# tachstrip.net
KiCad netlist of a schematic drawn in EAGLE
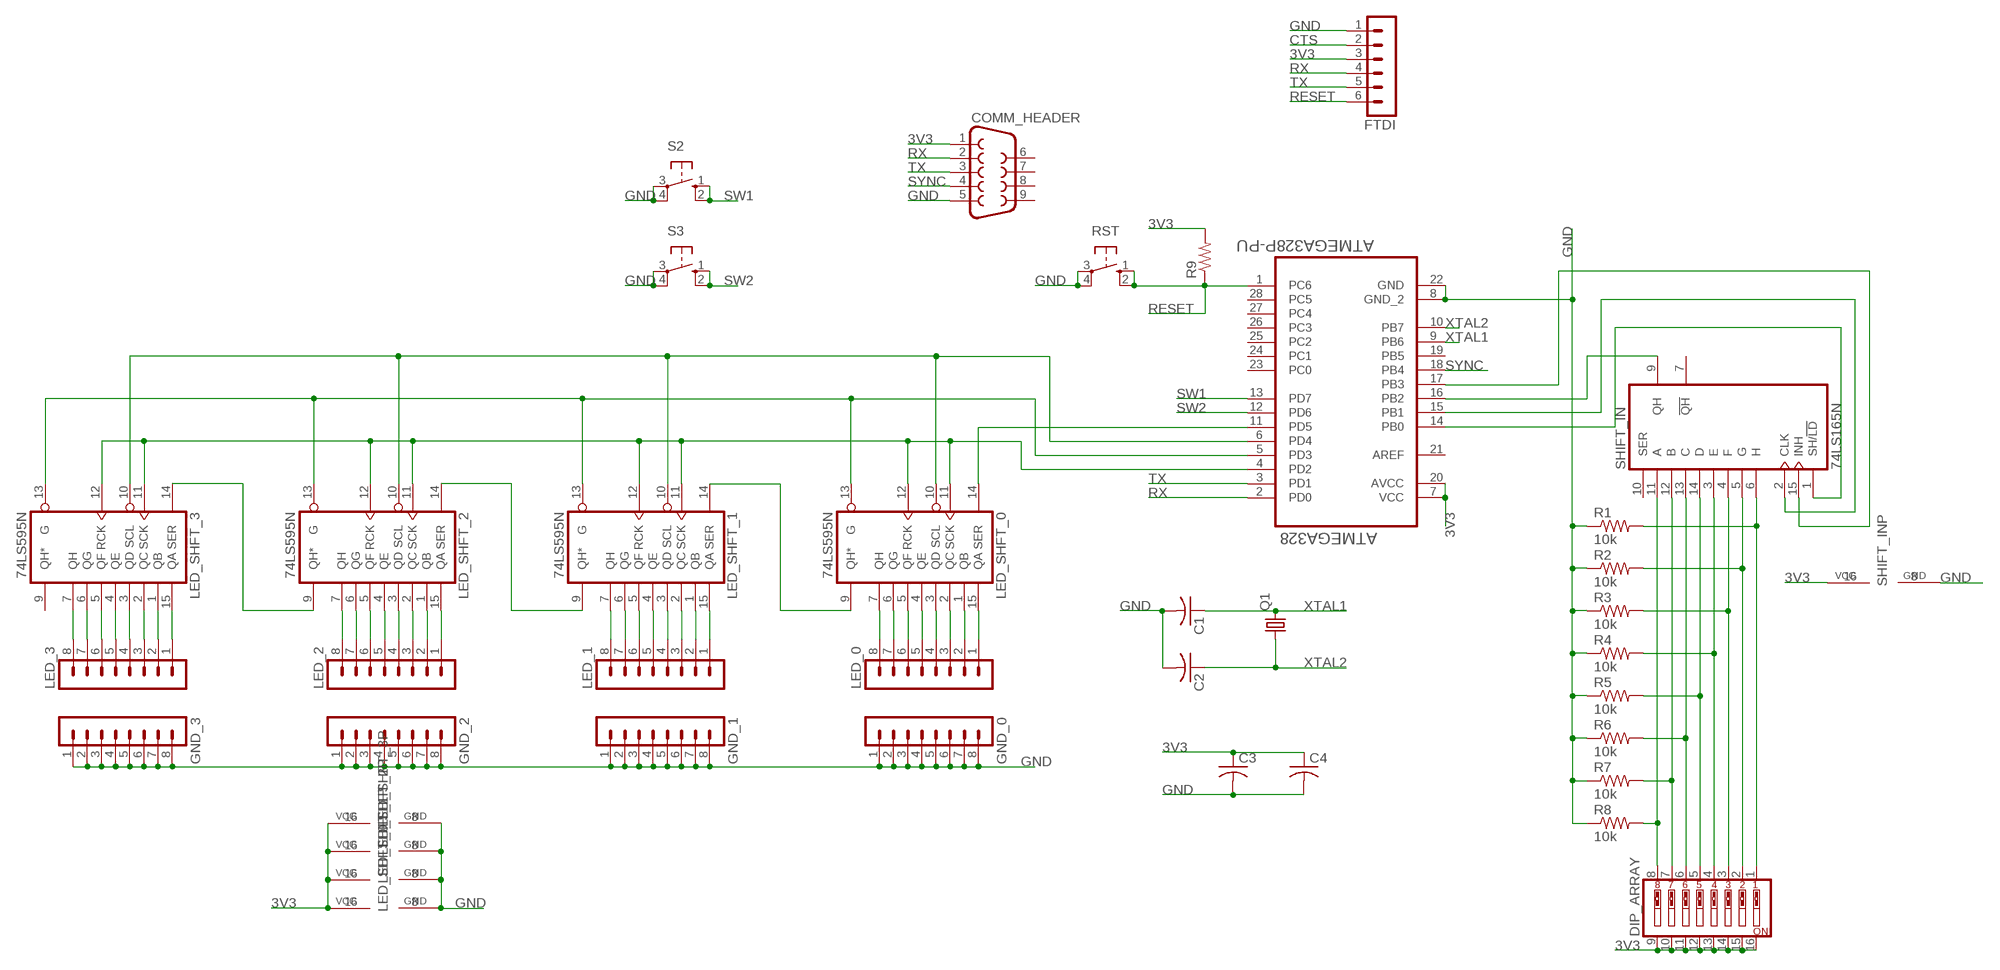
[diagram p0: schematic, sheet 1]

(export (version "E")
  (design (tool "Eeschema 10.0.6"))
  (components
    (comp (ref "ATMEGA328")
      (value "ATMEGA328P-PU")
      (footprint "eagle-import:DIP254P762X457-28")
      (libsource (lib "eagle-import") (part "ATMEGA328P-PU"))
    )
    (comp (ref "C1")
      (value "C-US025-025X050")
      (footprint "eagle-import:C025-025X050")
      (libsource (lib "eagle-import") (part "C-US025-025X050"))
    )
    (comp (ref "C2")
      (value "C-US025-025X050")
      (footprint "eagle-import:C025-025X050")
      (libsource (lib "eagle-import") (part "C-US025-025X050"))
    )
    (comp (ref "C3")
      (value "C-US025-025X050")
      (footprint "eagle-import:C025-025X050")
      (libsource (lib "eagle-import") (part "C-US025-025X050"))
    )
    (comp (ref "C4")
      (value "C-US025-025X050")
      (footprint "eagle-import:C025-025X050")
      (libsource (lib "eagle-import") (part "C-US025-025X050"))
    )
    (comp (ref "COMM_HEADER")
      (value "F09VB")
      (footprint "eagle-import:F09VB")
      (libsource (lib "eagle-import") (part "F09VB"))
    )
    (comp (ref "DIP_ARRAY")
      (value "SW_DIP-8")
      (footprint "eagle-import:DIPSWITCH-08")
      (libsource (lib "eagle-import") (part "SW_DIP-8"))
    )
    (comp (ref "FTDI")
      (value "MA06-1")
      (footprint "eagle-import:MA06-1")
      (libsource (lib "eagle-import") (part "MA06-1"))
    )
    (comp (ref "GND_0")
      (value "MA08-1")
      (footprint "eagle-import:MA08-1")
      (libsource (lib "eagle-import") (part "MA08-1"))
    )
    (comp (ref "GND_1")
      (value "MA08-1")
      (footprint "eagle-import:MA08-1")
      (libsource (lib "eagle-import") (part "MA08-1"))
    )
    (comp (ref "GND_2")
      (value "MA08-1")
      (footprint "eagle-import:MA08-1")
      (libsource (lib "eagle-import") (part "MA08-1"))
    )
    (comp (ref "GND_3")
      (value "MA08-1")
      (footprint "eagle-import:MA08-1")
      (libsource (lib "eagle-import") (part "MA08-1"))
    )
    (comp (ref "LED_0")
      (value "MA08-1")
      (footprint "eagle-import:MA08-1")
      (libsource (lib "eagle-import") (part "MA08-1"))
    )
    (comp (ref "LED_1")
      (value "MA08-1")
      (footprint "eagle-import:MA08-1")
      (libsource (lib "eagle-import") (part "MA08-1"))
    )
    (comp (ref "LED_2")
      (value "MA08-1")
      (footprint "eagle-import:MA08-1")
      (libsource (lib "eagle-import") (part "MA08-1"))
    )
    (comp (ref "LED_3")
      (value "MA08-1")
      (footprint "eagle-import:MA08-1")
      (libsource (lib "eagle-import") (part "MA08-1"))
    )
    (comp (ref "LED_SHFT_0")
      (value "74LS595N")
      (footprint "eagle-import:DIL16")
      (libsource (lib "eagle-import") (part "74595NLS"))
    )
    (comp (ref "LED_SHFT_1")
      (value "74LS595N")
      (footprint "eagle-import:DIL16")
      (libsource (lib "eagle-import") (part "74595NLS"))
    )
    (comp (ref "LED_SHFT_2")
      (value "74LS595N")
      (footprint "eagle-import:DIL16")
      (libsource (lib "eagle-import") (part "74595NLS"))
    )
    (comp (ref "LED_SHFT_3")
      (value "74LS595N")
      (footprint "eagle-import:DIL16")
      (libsource (lib "eagle-import") (part "74595NLS"))
    )
    (comp (ref "Q1")
      (value "CRYSTALHC49S")
      (footprint "eagle-import:HC49_S")
      (libsource (lib "eagle-import") (part "CRYSTALHC49S"))
    )
    (comp (ref "R1")
      (value "10k")
      (footprint "eagle-import:0204_5")
      (libsource (lib "eagle-import") (part "resistor_R-US_0204/5"))
    )
    (comp (ref "R2")
      (value "10k")
      (footprint "eagle-import:0204_5")
      (libsource (lib "eagle-import") (part "resistor_R-US_0204/5"))
    )
    (comp (ref "R3")
      (value "10k")
      (footprint "eagle-import:0204_5")
      (libsource (lib "eagle-import") (part "resistor_R-US_0204/5"))
    )
    (comp (ref "R4")
      (value "10k")
      (footprint "eagle-import:0204_5")
      (libsource (lib "eagle-import") (part "resistor_R-US_0204/5"))
    )
    (comp (ref "R5")
      (value "10k")
      (footprint "eagle-import:0204_5")
      (libsource (lib "eagle-import") (part "resistor_R-US_0204/5"))
    )
    (comp (ref "R6")
      (value "10k")
      (footprint "eagle-import:0204_5")
      (libsource (lib "eagle-import") (part "resistor_R-US_0204/5"))
    )
    (comp (ref "R7")
      (value "10k")
      (footprint "eagle-import:0204_5")
      (libsource (lib "eagle-import") (part "resistor_R-US_0204/5"))
    )
    (comp (ref "R8")
      (value "10k")
      (footprint "eagle-import:0204_5")
      (libsource (lib "eagle-import") (part "resistor_R-US_0204/5"))
    )
    (comp (ref "R9")
      (value "R-US_0204/7")
      (footprint "eagle-import:0204_7")
      (libsource (lib "eagle-import") (part "R-US_0204/7"))
    )
    (comp (ref "RST")
      (value "10-XX")
      (footprint "eagle-import:B3F-10XX")
      (fields (field (name "MPN") "B3F-1000"))
      (libsource (lib "eagle-import") (part "10-XX"))
    )
    (comp (ref "S2")
      (value "10-XX")
      (footprint "eagle-import:B3F-10XX")
      (fields (field (name "MPN") "B3F-1000"))
      (libsource (lib "eagle-import") (part "10-XX"))
    )
    (comp (ref "S3")
      (value "10-XX")
      (footprint "eagle-import:B3F-10XX")
      (fields (field (name "MPN") "B3F-1000"))
      (libsource (lib "eagle-import") (part "10-XX"))
    )
    (comp (ref "SHIFT_IN")
      (value "74LS165N")
      (footprint "eagle-import:DIL16")
      (libsource (lib "eagle-import") (part "74165NLS"))
    )
  )
  (nets
    (net (code "1") (name "/3V3") (class "Default")
      (node (ref "ATMEGA328") (pin "20") (pinfunction "AVCC_20") (pintype "power_in"))
      (node (ref "ATMEGA328") (pin "7") (pinfunction "VCC_7") (pintype "power_in"))
      (node (ref "C3") (pin "1") (pinfunction "1_1") (pintype "passive"))
      (node (ref "C4") (pin "1") (pinfunction "1_1") (pintype "passive"))
      (node (ref "COMM_HEADER") (pin "1") (pinfunction "1_1") (pintype "passive"))
      (node (ref "DIP_ARRAY") (pin "10") (pinfunction "10_10") (pintype "passive"))
      (node (ref "DIP_ARRAY") (pin "11") (pinfunction "11_11") (pintype "passive"))
      (node (ref "DIP_ARRAY") (pin "12") (pinfunction "12_12") (pintype "passive"))
      (node (ref "DIP_ARRAY") (pin "13") (pinfunction "13_13") (pintype "passive"))
      (node (ref "DIP_ARRAY") (pin "14") (pinfunction "14_14") (pintype "passive"))
      (node (ref "DIP_ARRAY") (pin "15") (pinfunction "15_15") (pintype "passive"))
      (node (ref "DIP_ARRAY") (pin "16") (pinfunction "16_16") (pintype "passive"))
      (node (ref "DIP_ARRAY") (pin "9") (pinfunction "9_9") (pintype "passive"))
      (node (ref "FTDI") (pin "3") (pinfunction "3_3") (pintype "passive"))
      (node (ref "LED_SHFT_0") (pin "16") (pinfunction "VCC_16") (pintype "power_in"))
      (node (ref "LED_SHFT_1") (pin "16") (pinfunction "VCC_16") (pintype "power_in"))
      (node (ref "LED_SHFT_2") (pin "16") (pinfunction "VCC_16") (pintype "power_in"))
      (node (ref "LED_SHFT_3") (pin "16") (pinfunction "VCC_16") (pintype "power_in"))
      (node (ref "R9") (pin "2") (pinfunction "2_2") (pintype "passive"))
      (node (ref "SHIFT_IN") (pin "16") (pinfunction "VCC_16") (pintype "power_in"))
    )
    (net (code "2") (name "/CTS") (class "Default")
      (node (ref "FTDI") (pin "2") (pinfunction "2_2") (pintype "passive"))
    )
    (net (code "3") (name "/GND") (class "Default")
      (node (ref "ATMEGA328") (pin "22") (pinfunction "GND_22") (pintype "passive"))
      (node (ref "ATMEGA328") (pin "8") (pinfunction "GND_2_8") (pintype "passive"))
      (node (ref "C1") (pin "2") (pinfunction "2_2") (pintype "passive"))
      (node (ref "C2") (pin "2") (pinfunction "2_2") (pintype "passive"))
      (node (ref "C3") (pin "2") (pinfunction "2_2") (pintype "passive"))
      (node (ref "C4") (pin "2") (pinfunction "2_2") (pintype "passive"))
      (node (ref "COMM_HEADER") (pin "5") (pinfunction "5_5") (pintype "passive"))
      (node (ref "FTDI") (pin "1") (pinfunction "1_1") (pintype "passive"))
      (node (ref "GND_0") (pin "1") (pinfunction "1_1") (pintype "passive"))
      (node (ref "GND_0") (pin "2") (pinfunction "2_2") (pintype "passive"))
      (node (ref "GND_0") (pin "3") (pinfunction "3_3") (pintype "passive"))
      (node (ref "GND_0") (pin "4") (pinfunction "4_4") (pintype "passive"))
      (node (ref "GND_0") (pin "5") (pinfunction "5_5") (pintype "passive"))
      (node (ref "GND_0") (pin "6") (pinfunction "6_6") (pintype "passive"))
      (node (ref "GND_0") (pin "7") (pinfunction "7_7") (pintype "passive"))
      (node (ref "GND_0") (pin "8") (pinfunction "8_8") (pintype "passive"))
      (node (ref "GND_1") (pin "1") (pinfunction "1_1") (pintype "passive"))
      (node (ref "GND_1") (pin "2") (pinfunction "2_2") (pintype "passive"))
      (node (ref "GND_1") (pin "3") (pinfunction "3_3") (pintype "passive"))
      (node (ref "GND_1") (pin "4") (pinfunction "4_4") (pintype "passive"))
      (node (ref "GND_1") (pin "5") (pinfunction "5_5") (pintype "passive"))
      (node (ref "GND_1") (pin "6") (pinfunction "6_6") (pintype "passive"))
      (node (ref "GND_1") (pin "7") (pinfunction "7_7") (pintype "passive"))
      (node (ref "GND_1") (pin "8") (pinfunction "8_8") (pintype "passive"))
      (node (ref "GND_2") (pin "1") (pinfunction "1_1") (pintype "passive"))
      (node (ref "GND_2") (pin "2") (pinfunction "2_2") (pintype "passive"))
      (node (ref "GND_2") (pin "3") (pinfunction "3_3") (pintype "passive"))
      (node (ref "GND_2") (pin "4") (pinfunction "4_4") (pintype "passive"))
      (node (ref "GND_2") (pin "5") (pinfunction "5_5") (pintype "passive"))
      (node (ref "GND_2") (pin "6") (pinfunction "6_6") (pintype "passive"))
      (node (ref "GND_2") (pin "7") (pinfunction "7_7") (pintype "passive"))
      (node (ref "GND_2") (pin "8") (pinfunction "8_8") (pintype "passive"))
      (node (ref "GND_3") (pin "1") (pinfunction "1_1") (pintype "passive"))
      (node (ref "GND_3") (pin "2") (pinfunction "2_2") (pintype "passive"))
      (node (ref "GND_3") (pin "3") (pinfunction "3_3") (pintype "passive"))
      (node (ref "GND_3") (pin "4") (pinfunction "4_4") (pintype "passive"))
      (node (ref "GND_3") (pin "5") (pinfunction "5_5") (pintype "passive"))
      (node (ref "GND_3") (pin "6") (pinfunction "6_6") (pintype "passive"))
      (node (ref "GND_3") (pin "7") (pinfunction "7_7") (pintype "passive"))
      (node (ref "GND_3") (pin "8") (pinfunction "8_8") (pintype "passive"))
      (node (ref "LED_SHFT_0") (pin "8") (pinfunction "GND_8") (pintype "power_in"))
      (node (ref "LED_SHFT_1") (pin "8") (pinfunction "GND_8") (pintype "power_in"))
      (node (ref "LED_SHFT_2") (pin "8") (pinfunction "GND_8") (pintype "power_in"))
      (node (ref "LED_SHFT_3") (pin "8") (pinfunction "GND_8") (pintype "power_in"))
      (node (ref "R1") (pin "1") (pinfunction "1_1") (pintype "passive"))
      (node (ref "R2") (pin "1") (pinfunction "1_1") (pintype "passive"))
      (node (ref "R3") (pin "1") (pinfunction "1_1") (pintype "passive"))
      (node (ref "R4") (pin "1") (pinfunction "1_1") (pintype "passive"))
      (node (ref "R5") (pin "1") (pinfunction "1_1") (pintype "passive"))
      (node (ref "R6") (pin "1") (pinfunction "1_1") (pintype "passive"))
      (node (ref "R7") (pin "1") (pinfunction "1_1") (pintype "passive"))
      (node (ref "R8") (pin "1") (pinfunction "1_1") (pintype "passive"))
      (node (ref "RST") (pin "3") (pinfunction "P_3") (pintype "passive"))
      (node (ref "RST") (pin "4") (pinfunction "P1_4") (pintype "passive"))
      (node (ref "S2") (pin "3") (pinfunction "P_3") (pintype "passive"))
      (node (ref "S2") (pin "4") (pinfunction "P1_4") (pintype "passive"))
      (node (ref "S3") (pin "3") (pinfunction "P_3") (pintype "passive"))
      (node (ref "S3") (pin "4") (pinfunction "P1_4") (pintype "passive"))
      (node (ref "SHIFT_IN") (pin "8") (pinfunction "GND_8") (pintype "power_in"))
    )
    (net (code "4") (name "/RESET") (class "Default")
      (node (ref "ATMEGA328") (pin "1") (pinfunction "PC6_1") (pintype "bidirectional"))
      (node (ref "FTDI") (pin "6") (pinfunction "6_6") (pintype "passive"))
      (node (ref "R9") (pin "1") (pinfunction "1_1") (pintype "passive"))
      (node (ref "RST") (pin "1") (pinfunction "S_1") (pintype "passive"))
      (node (ref "RST") (pin "2") (pinfunction "S1_2") (pintype "passive"))
    )
    (net (code "5") (name "/RX") (class "Default")
      (node (ref "ATMEGA328") (pin "2") (pinfunction "PD0_2") (pintype "bidirectional"))
      (node (ref "COMM_HEADER") (pin "2") (pinfunction "2_2") (pintype "passive"))
      (node (ref "FTDI") (pin "4") (pinfunction "4_4") (pintype "passive"))
    )
    (net (code "6") (name "/SW1") (class "Default")
      (node (ref "ATMEGA328") (pin "13") (pinfunction "PD7_13") (pintype "bidirectional"))
      (node (ref "S2") (pin "1") (pinfunction "S_1") (pintype "passive"))
      (node (ref "S2") (pin "2") (pinfunction "S1_2") (pintype "passive"))
    )
    (net (code "7") (name "/SW2") (class "Default")
      (node (ref "ATMEGA328") (pin "12") (pinfunction "PD6_12") (pintype "bidirectional"))
      (node (ref "S3") (pin "1") (pinfunction "S_1") (pintype "passive"))
      (node (ref "S3") (pin "2") (pinfunction "S1_2") (pintype "passive"))
    )
    (net (code "8") (name "/SYNC") (class "Default")
      (node (ref "ATMEGA328") (pin "18") (pinfunction "PB4_18") (pintype "bidirectional"))
      (node (ref "COMM_HEADER") (pin "4") (pinfunction "4_4") (pintype "passive"))
    )
    (net (code "9") (name "/TX") (class "Default")
      (node (ref "ATMEGA328") (pin "3") (pinfunction "PD1_3") (pintype "bidirectional"))
      (node (ref "COMM_HEADER") (pin "3") (pinfunction "3_3") (pintype "passive"))
      (node (ref "FTDI") (pin "5") (pinfunction "5_5") (pintype "passive"))
    )
    (net (code "10") (name "/XTAL1") (class "Default")
      (node (ref "ATMEGA328") (pin "9") (pinfunction "PB6_9") (pintype "bidirectional"))
      (node (ref "C1") (pin "1") (pinfunction "1_1") (pintype "passive"))
      (node (ref "Q1") (pin "2") (pinfunction "2_2") (pintype "passive"))
    )
    (net (code "11") (name "/XTAL2") (class "Default")
      (node (ref "ATMEGA328") (pin "10") (pinfunction "PB7_10") (pintype "bidirectional"))
      (node (ref "C2") (pin "1") (pinfunction "1_1") (pintype "passive"))
      (node (ref "Q1") (pin "1") (pinfunction "1_1") (pintype "passive"))
    )
    (net (code "12") (name "Net-(ATMEGA328-PB0)") (class "Default")
      (node (ref "ATMEGA328") (pin "14") (pinfunction "PB0_14") (pintype "bidirectional"))
      (node (ref "SHIFT_IN") (pin "1") (pinfunction "SH/~{LD}_1") (pintype "input"))
    )
    (net (code "13") (name "Net-(ATMEGA328-PB1)") (class "Default")
      (node (ref "ATMEGA328") (pin "15") (pinfunction "PB1_15") (pintype "bidirectional"))
      (node (ref "SHIFT_IN") (pin "2") (pinfunction "CLK_2") (pintype "input"))
    )
    (net (code "14") (name "Net-(ATMEGA328-PB2)") (class "Default")
      (node (ref "ATMEGA328") (pin "16") (pinfunction "PB2_16") (pintype "bidirectional"))
      (node (ref "SHIFT_IN") (pin "9") (pinfunction "QH_9") (pintype "output"))
    )
    (net (code "15") (name "Net-(ATMEGA328-PB3)") (class "Default")
      (node (ref "ATMEGA328") (pin "17") (pinfunction "PB3_17") (pintype "bidirectional"))
      (node (ref "SHIFT_IN") (pin "15") (pinfunction "INH_15") (pintype "input"))
    )
    (net (code "16") (name "Net-(ATMEGA328-PD2)") (class "Default")
      (node (ref "ATMEGA328") (pin "4") (pinfunction "PD2_4") (pintype "bidirectional"))
      (node (ref "LED_SHFT_0") (pin "11") (pinfunction "SCK_11") (pintype "input"))
      (node (ref "LED_SHFT_0") (pin "12") (pinfunction "RCK_12") (pintype "input"))
      (node (ref "LED_SHFT_1") (pin "11") (pinfunction "SCK_11") (pintype "input"))
      (node (ref "LED_SHFT_1") (pin "12") (pinfunction "RCK_12") (pintype "input"))
      (node (ref "LED_SHFT_2") (pin "11") (pinfunction "SCK_11") (pintype "input"))
      (node (ref "LED_SHFT_2") (pin "12") (pinfunction "RCK_12") (pintype "input"))
      (node (ref "LED_SHFT_3") (pin "11") (pinfunction "SCK_11") (pintype "input"))
      (node (ref "LED_SHFT_3") (pin "12") (pinfunction "RCK_12") (pintype "input"))
    )
    (net (code "17") (name "Net-(ATMEGA328-PD3)") (class "Default")
      (node (ref "ATMEGA328") (pin "5") (pinfunction "PD3_5") (pintype "bidirectional"))
      (node (ref "LED_SHFT_0") (pin "13") (pinfunction "G_13") (pintype "input"))
      (node (ref "LED_SHFT_1") (pin "13") (pinfunction "G_13") (pintype "input"))
      (node (ref "LED_SHFT_2") (pin "13") (pinfunction "G_13") (pintype "input"))
      (node (ref "LED_SHFT_3") (pin "13") (pinfunction "G_13") (pintype "input"))
    )
    (net (code "18") (name "Net-(ATMEGA328-PD4)") (class "Default")
      (node (ref "ATMEGA328") (pin "6") (pinfunction "PD4_6") (pintype "bidirectional"))
      (node (ref "LED_SHFT_0") (pin "10") (pinfunction "SCL_10") (pintype "input"))
      (node (ref "LED_SHFT_1") (pin "10") (pinfunction "SCL_10") (pintype "input"))
      (node (ref "LED_SHFT_2") (pin "10") (pinfunction "SCL_10") (pintype "input"))
      (node (ref "LED_SHFT_3") (pin "10") (pinfunction "SCL_10") (pintype "input"))
    )
    (net (code "19") (name "Net-(ATMEGA328-PD5)") (class "Default")
      (node (ref "ATMEGA328") (pin "11") (pinfunction "PD5_11") (pintype "bidirectional"))
      (node (ref "LED_SHFT_0") (pin "14") (pinfunction "SER_14") (pintype "input"))
    )
    (net (code "20") (name "Net-(LED_SHFT_0A-QA)") (class "Default")
      (node (ref "LED_0") (pin "1") (pinfunction "1_1") (pintype "passive"))
      (node (ref "LED_SHFT_0") (pin "15") (pinfunction "QA_15") (pintype "tri_state"))
    )
    (net (code "21") (name "Net-(LED_SHFT_0A-QB)") (class "Default")
      (node (ref "LED_0") (pin "2") (pinfunction "2_2") (pintype "passive"))
      (node (ref "LED_SHFT_0") (pin "1") (pinfunction "QB_1") (pintype "tri_state"))
    )
    (net (code "22") (name "Net-(LED_SHFT_0A-QC)") (class "Default")
      (node (ref "LED_0") (pin "3") (pinfunction "3_3") (pintype "passive"))
      (node (ref "LED_SHFT_0") (pin "2") (pinfunction "QC_2") (pintype "tri_state"))
    )
    (net (code "23") (name "Net-(LED_SHFT_0A-QD)") (class "Default")
      (node (ref "LED_0") (pin "4") (pinfunction "4_4") (pintype "passive"))
      (node (ref "LED_SHFT_0") (pin "3") (pinfunction "QD_3") (pintype "tri_state"))
    )
    (net (code "24") (name "Net-(LED_SHFT_0A-QE)") (class "Default")
      (node (ref "LED_0") (pin "5") (pinfunction "5_5") (pintype "passive"))
      (node (ref "LED_SHFT_0") (pin "4") (pinfunction "QE_4") (pintype "tri_state"))
    )
    (net (code "25") (name "Net-(LED_SHFT_0A-QF)") (class "Default")
      (node (ref "LED_0") (pin "6") (pinfunction "6_6") (pintype "passive"))
      (node (ref "LED_SHFT_0") (pin "5") (pinfunction "QF_5") (pintype "tri_state"))
    )
    (net (code "26") (name "Net-(LED_SHFT_0A-QG)") (class "Default")
      (node (ref "LED_0") (pin "7") (pinfunction "7_7") (pintype "passive"))
      (node (ref "LED_SHFT_0") (pin "6") (pinfunction "QG_6") (pintype "tri_state"))
    )
    (net (code "27") (name "Net-(LED_SHFT_0A-QH)") (class "Default")
      (node (ref "LED_0") (pin "8") (pinfunction "8_8") (pintype "passive"))
      (node (ref "LED_SHFT_0") (pin "7") (pinfunction "QH_7") (pintype "tri_state"))
    )
    (net (code "28") (name "Net-(LED_SHFT_0A-QH*)") (class "Default")
      (node (ref "LED_SHFT_0") (pin "9") (pinfunction "QH*_9") (pintype "tri_state"))
      (node (ref "LED_SHFT_1") (pin "14") (pinfunction "SER_14") (pintype "input"))
    )
    (net (code "29") (name "Net-(LED_SHFT_1A-QA)") (class "Default")
      (node (ref "LED_1") (pin "1") (pinfunction "1_1") (pintype "passive"))
      (node (ref "LED_SHFT_1") (pin "15") (pinfunction "QA_15") (pintype "tri_state"))
    )
    (net (code "30") (name "Net-(LED_SHFT_1A-QB)") (class "Default")
      (node (ref "LED_1") (pin "2") (pinfunction "2_2") (pintype "passive"))
      (node (ref "LED_SHFT_1") (pin "1") (pinfunction "QB_1") (pintype "tri_state"))
    )
    (net (code "31") (name "Net-(LED_SHFT_1A-QC)") (class "Default")
      (node (ref "LED_1") (pin "3") (pinfunction "3_3") (pintype "passive"))
      (node (ref "LED_SHFT_1") (pin "2") (pinfunction "QC_2") (pintype "tri_state"))
    )
    (net (code "32") (name "Net-(LED_SHFT_1A-QD)") (class "Default")
      (node (ref "LED_1") (pin "4") (pinfunction "4_4") (pintype "passive"))
      (node (ref "LED_SHFT_1") (pin "3") (pinfunction "QD_3") (pintype "tri_state"))
    )
    (net (code "33") (name "Net-(LED_SHFT_1A-QE)") (class "Default")
      (node (ref "LED_1") (pin "5") (pinfunction "5_5") (pintype "passive"))
      (node (ref "LED_SHFT_1") (pin "4") (pinfunction "QE_4") (pintype "tri_state"))
    )
    (net (code "34") (name "Net-(LED_SHFT_1A-QF)") (class "Default")
      (node (ref "LED_1") (pin "6") (pinfunction "6_6") (pintype "passive"))
      (node (ref "LED_SHFT_1") (pin "5") (pinfunction "QF_5") (pintype "tri_state"))
    )
    (net (code "35") (name "Net-(LED_SHFT_1A-QG)") (class "Default")
      (node (ref "LED_1") (pin "7") (pinfunction "7_7") (pintype "passive"))
      (node (ref "LED_SHFT_1") (pin "6") (pinfunction "QG_6") (pintype "tri_state"))
    )
    (net (code "36") (name "Net-(LED_SHFT_1A-QH)") (class "Default")
      (node (ref "LED_1") (pin "8") (pinfunction "8_8") (pintype "passive"))
      (node (ref "LED_SHFT_1") (pin "7") (pinfunction "QH_7") (pintype "tri_state"))
    )
    (net (code "37") (name "Net-(LED_SHFT_1A-QH*)") (class "Default")
      (node (ref "LED_SHFT_1") (pin "9") (pinfunction "QH*_9") (pintype "tri_state"))
      (node (ref "LED_SHFT_2") (pin "14") (pinfunction "SER_14") (pintype "input"))
    )
    (net (code "38") (name "Net-(LED_SHFT_2A-QA)") (class "Default")
      (node (ref "LED_2") (pin "1") (pinfunction "1_1") (pintype "passive"))
      (node (ref "LED_SHFT_2") (pin "15") (pinfunction "QA_15") (pintype "tri_state"))
    )
    (net (code "39") (name "Net-(LED_SHFT_2A-QB)") (class "Default")
      (node (ref "LED_2") (pin "2") (pinfunction "2_2") (pintype "passive"))
      (node (ref "LED_SHFT_2") (pin "1") (pinfunction "QB_1") (pintype "tri_state"))
    )
    (net (code "40") (name "Net-(LED_SHFT_2A-QC)") (class "Default")
      (node (ref "LED_2") (pin "3") (pinfunction "3_3") (pintype "passive"))
      (node (ref "LED_SHFT_2") (pin "2") (pinfunction "QC_2") (pintype "tri_state"))
    )
    (net (code "41") (name "Net-(LED_SHFT_2A-QD)") (class "Default")
      (node (ref "LED_2") (pin "4") (pinfunction "4_4") (pintype "passive"))
      (node (ref "LED_SHFT_2") (pin "3") (pinfunction "QD_3") (pintype "tri_state"))
    )
    (net (code "42") (name "Net-(LED_SHFT_2A-QE)") (class "Default")
      (node (ref "LED_2") (pin "5") (pinfunction "5_5") (pintype "passive"))
      (node (ref "LED_SHFT_2") (pin "4") (pinfunction "QE_4") (pintype "tri_state"))
    )
    (net (code "43") (name "Net-(LED_SHFT_2A-QF)") (class "Default")
      (node (ref "LED_2") (pin "6") (pinfunction "6_6") (pintype "passive"))
      (node (ref "LED_SHFT_2") (pin "5") (pinfunction "QF_5") (pintype "tri_state"))
    )
    (net (code "44") (name "Net-(LED_SHFT_2A-QG)") (class "Default")
      (node (ref "LED_2") (pin "7") (pinfunction "7_7") (pintype "passive"))
      (node (ref "LED_SHFT_2") (pin "6") (pinfunction "QG_6") (pintype "tri_state"))
    )
    (net (code "45") (name "Net-(LED_SHFT_2A-QH)") (class "Default")
      (node (ref "LED_2") (pin "8") (pinfunction "8_8") (pintype "passive"))
      (node (ref "LED_SHFT_2") (pin "7") (pinfunction "QH_7") (pintype "tri_state"))
    )
    (net (code "46") (name "Net-(LED_SHFT_2A-QH*)") (class "Default")
      (node (ref "LED_SHFT_2") (pin "9") (pinfunction "QH*_9") (pintype "tri_state"))
      (node (ref "LED_SHFT_3") (pin "14") (pinfunction "SER_14") (pintype "input"))
    )
    (net (code "47") (name "Net-(LED_SHFT_3A-QA)") (class "Default")
      (node (ref "LED_3") (pin "1") (pinfunction "1_1") (pintype "passive"))
      (node (ref "LED_SHFT_3") (pin "15") (pinfunction "QA_15") (pintype "tri_state"))
    )
    (net (code "48") (name "Net-(LED_SHFT_3A-QB)") (class "Default")
      (node (ref "LED_3") (pin "2") (pinfunction "2_2") (pintype "passive"))
      (node (ref "LED_SHFT_3") (pin "1") (pinfunction "QB_1") (pintype "tri_state"))
    )
    (net (code "49") (name "Net-(LED_SHFT_3A-QC)") (class "Default")
      (node (ref "LED_3") (pin "3") (pinfunction "3_3") (pintype "passive"))
      (node (ref "LED_SHFT_3") (pin "2") (pinfunction "QC_2") (pintype "tri_state"))
    )
    (net (code "50") (name "Net-(LED_SHFT_3A-QD)") (class "Default")
      (node (ref "LED_3") (pin "4") (pinfunction "4_4") (pintype "passive"))
      (node (ref "LED_SHFT_3") (pin "3") (pinfunction "QD_3") (pintype "tri_state"))
    )
    (net (code "51") (name "Net-(LED_SHFT_3A-QE)") (class "Default")
      (node (ref "LED_3") (pin "5") (pinfunction "5_5") (pintype "passive"))
      (node (ref "LED_SHFT_3") (pin "4") (pinfunction "QE_4") (pintype "tri_state"))
    )
    (net (code "52") (name "Net-(LED_SHFT_3A-QF)") (class "Default")
      (node (ref "LED_3") (pin "6") (pinfunction "6_6") (pintype "passive"))
      (node (ref "LED_SHFT_3") (pin "5") (pinfunction "QF_5") (pintype "tri_state"))
    )
    (net (code "53") (name "Net-(LED_SHFT_3A-QG)") (class "Default")
      (node (ref "LED_3") (pin "7") (pinfunction "7_7") (pintype "passive"))
      (node (ref "LED_SHFT_3") (pin "6") (pinfunction "QG_6") (pintype "tri_state"))
    )
    (net (code "54") (name "Net-(LED_SHFT_3A-QH)") (class "Default")
      (node (ref "LED_3") (pin "8") (pinfunction "8_8") (pintype "passive"))
      (node (ref "LED_SHFT_3") (pin "7") (pinfunction "QH_7") (pintype "tri_state"))
    )
    (net (code "55") (name "Net-(SHIFT_INA-A)") (class "Default")
      (node (ref "DIP_ARRAY") (pin "8") (pinfunction "8_8") (pintype "passive"))
      (node (ref "R8") (pin "2") (pinfunction "2_2") (pintype "passive"))
      (node (ref "SHIFT_IN") (pin "11") (pinfunction "A_11") (pintype "input"))
    )
    (net (code "56") (name "Net-(SHIFT_INA-B)") (class "Default")
      (node (ref "DIP_ARRAY") (pin "7") (pinfunction "7_7") (pintype "passive"))
      (node (ref "R7") (pin "2") (pinfunction "2_2") (pintype "passive"))
      (node (ref "SHIFT_IN") (pin "12") (pinfunction "B_12") (pintype "input"))
    )
    (net (code "57") (name "Net-(SHIFT_INA-C)") (class "Default")
      (node (ref "DIP_ARRAY") (pin "6") (pinfunction "6_6") (pintype "passive"))
      (node (ref "R6") (pin "2") (pinfunction "2_2") (pintype "passive"))
      (node (ref "SHIFT_IN") (pin "13") (pinfunction "C_13") (pintype "input"))
    )
    (net (code "58") (name "Net-(SHIFT_INA-D)") (class "Default")
      (node (ref "DIP_ARRAY") (pin "5") (pinfunction "5_5") (pintype "passive"))
      (node (ref "R5") (pin "2") (pinfunction "2_2") (pintype "passive"))
      (node (ref "SHIFT_IN") (pin "14") (pinfunction "D_14") (pintype "input"))
    )
    (net (code "59") (name "Net-(SHIFT_INA-E)") (class "Default")
      (node (ref "DIP_ARRAY") (pin "4") (pinfunction "4_4") (pintype "passive"))
      (node (ref "R4") (pin "2") (pinfunction "2_2") (pintype "passive"))
      (node (ref "SHIFT_IN") (pin "3") (pinfunction "E_3") (pintype "input"))
    )
    (net (code "60") (name "Net-(SHIFT_INA-F)") (class "Default")
      (node (ref "DIP_ARRAY") (pin "3") (pinfunction "3_3") (pintype "passive"))
      (node (ref "R3") (pin "2") (pinfunction "2_2") (pintype "passive"))
      (node (ref "SHIFT_IN") (pin "4") (pinfunction "F_4") (pintype "input"))
    )
    (net (code "61") (name "Net-(SHIFT_INA-G)") (class "Default")
      (node (ref "DIP_ARRAY") (pin "2") (pinfunction "2_2") (pintype "passive"))
      (node (ref "R2") (pin "2") (pinfunction "2_2") (pintype "passive"))
      (node (ref "SHIFT_IN") (pin "5") (pinfunction "G_5") (pintype "input"))
    )
    (net (code "62") (name "Net-(SHIFT_INA-H)") (class "Default")
      (node (ref "DIP_ARRAY") (pin "1") (pinfunction "1_1") (pintype "passive"))
      (node (ref "R1") (pin "2") (pinfunction "2_2") (pintype "passive"))
      (node (ref "SHIFT_IN") (pin "6") (pinfunction "H_6") (pintype "input"))
    )
    (net (code "63") (name "unconnected-(ATMEGA328-AREF-Pad21)") (class "Default")
      (node (ref "ATMEGA328") (pin "21") (pinfunction "AREF_21") (pintype "input"))
    )
    (net (code "64") (name "unconnected-(ATMEGA328-PB5-Pad19)") (class "Default")
      (node (ref "ATMEGA328") (pin "19") (pinfunction "PB5_19") (pintype "bidirectional"))
    )
    (net (code "65") (name "unconnected-(ATMEGA328-PC0-Pad23)") (class "Default")
      (node (ref "ATMEGA328") (pin "23") (pinfunction "PC0_23") (pintype "bidirectional"))
    )
    (net (code "66") (name "unconnected-(ATMEGA328-PC1-Pad24)") (class "Default")
      (node (ref "ATMEGA328") (pin "24") (pinfunction "PC1_24") (pintype "bidirectional"))
    )
    (net (code "67") (name "unconnected-(ATMEGA328-PC2-Pad25)") (class "Default")
      (node (ref "ATMEGA328") (pin "25") (pinfunction "PC2_25") (pintype "bidirectional"))
    )
    (net (code "68") (name "unconnected-(ATMEGA328-PC3-Pad26)") (class "Default")
      (node (ref "ATMEGA328") (pin "26") (pinfunction "PC3_26") (pintype "bidirectional"))
    )
    (net (code "69") (name "unconnected-(ATMEGA328-PC4-Pad27)") (class "Default")
      (node (ref "ATMEGA328") (pin "27") (pinfunction "PC4_27") (pintype "bidirectional"))
    )
    (net (code "70") (name "unconnected-(ATMEGA328-PC5-Pad28)") (class "Default")
      (node (ref "ATMEGA328") (pin "28") (pinfunction "PC5_28") (pintype "bidirectional"))
    )
    (net (code "71") (name "unconnected-(COMM_HEADER-Pad6)") (class "Default")
      (node (ref "COMM_HEADER") (pin "6") (pinfunction "6_6") (pintype "passive"))
    )
    (net (code "72") (name "unconnected-(COMM_HEADER-Pad7)") (class "Default")
      (node (ref "COMM_HEADER") (pin "7") (pinfunction "7_7") (pintype "passive"))
    )
    (net (code "73") (name "unconnected-(COMM_HEADER-Pad8)") (class "Default")
      (node (ref "COMM_HEADER") (pin "8") (pinfunction "8_8") (pintype "passive"))
    )
    (net (code "74") (name "unconnected-(COMM_HEADER-Pad9)") (class "Default")
      (node (ref "COMM_HEADER") (pin "9") (pinfunction "9_9") (pintype "passive"))
    )
    (net (code "75") (name "unconnected-(LED_SHFT_3A-QH*-Pad9)") (class "Default")
      (node (ref "LED_SHFT_3") (pin "9") (pinfunction "QH*_9") (pintype "tri_state"))
    )
    (net (code "76") (name "unconnected-(SHIFT_INA-SER-Pad10)") (class "Default")
      (node (ref "SHIFT_IN") (pin "10") (pinfunction "SER_10") (pintype "input"))
    )
    (net (code "77") (name "unconnected-(SHIFT_INA-~{QH}-Pad7)") (class "Default")
      (node (ref "SHIFT_IN") (pin "7") (pinfunction "~{QH}_7") (pintype "output"))
    )
  )
)
